# Bandpass.net
KiCad netlist of a schematic drawn in Altium Designer
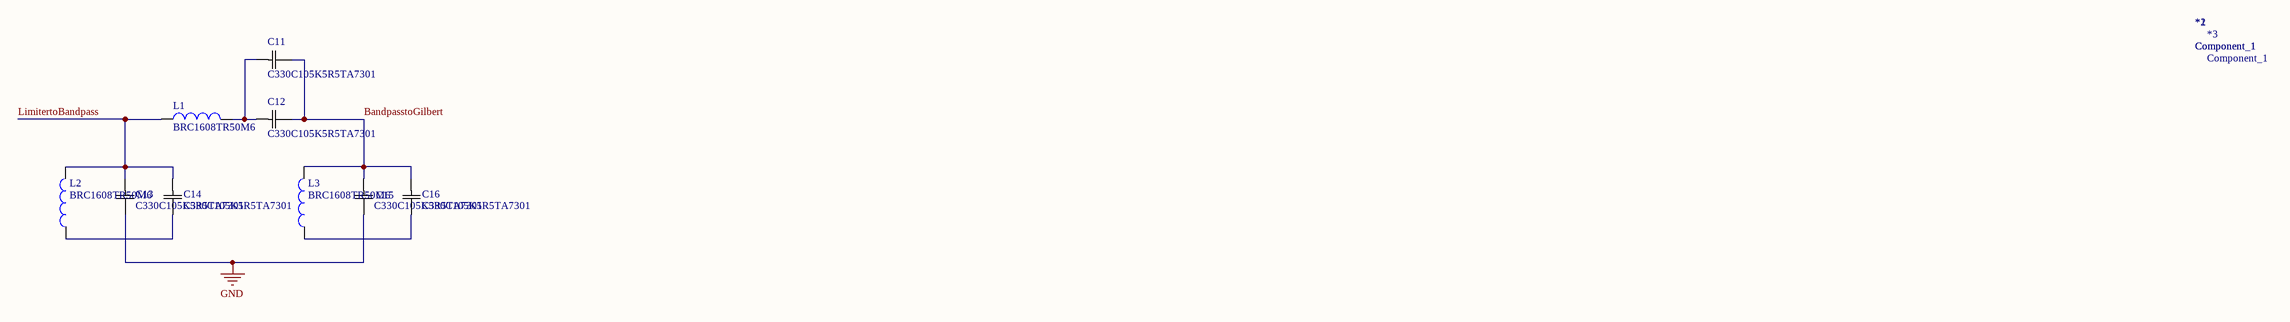
[diagram p0: Bandpass.SchDoc]

(export (version "E")
  (design (tool "Eeschema 10.0.6"))
  (components
    (comp (ref "*1") (value "Component_1") (libsource (lib "PRPC004SAAN-RC") (part "Component_1")))
    (comp (ref "*2") (value "Component_1") (libsource (lib "PRPC004SAAN-RC") (part "Component_1")))
    (comp (ref "*3") (value "Component_1") (libsource (lib "PRPC004SAAN-RC") (part "Component_1")))
    (comp (ref "C11")
      (value "C330C105K5R5TA7301")
      (footprint "CAP_C330C_MR_X7R_KEM")
      (description "No Description Available")
      (libsource (lib "C330C105K5R5TA7301") (part "C330C105K5R5TA7301"))
    )
    (comp (ref "C12")
      (value "C330C105K5R5TA7301")
      (footprint "CAP_C330C_MR_X7R_KEM")
      (description "No Description Available")
      (libsource (lib "C330C105K5R5TA7301") (part "C330C105K5R5TA7301"))
    )
    (comp (ref "C13")
      (value "C330C105K5R5TA7301")
      (footprint "CAP_C330C_MR_X7R_KEM")
      (description "No Description Available")
      (libsource (lib "C330C105K5R5TA7301") (part "C330C105K5R5TA7301"))
    )
    (comp (ref "C14")
      (value "C330C105K5R5TA7301")
      (footprint "CAP_C330C_MR_X7R_KEM")
      (description "No Description Available")
      (libsource (lib "C330C105K5R5TA7301") (part "C330C105K5R5TA7301"))
    )
    (comp (ref "C15")
      (value "C330C105K5R5TA7301")
      (footprint "CAP_C330C_MR_X7R_KEM")
      (description "No Description Available")
      (libsource (lib "C330C105K5R5TA7301") (part "C330C105K5R5TA7301"))
    )
    (comp (ref "C16")
      (value "C330C105K5R5TA7301")
      (footprint "CAP_C330C_MR_X7R_KEM")
      (description "No Description Available")
      (libsource (lib "C330C105K5R5TA7301") (part "C330C105K5R5TA7301"))
    )
    (comp (ref "L1")
      (value "BRC1608TR50M6")
      (footprint "INDC1608X100N")
      (description "Inductor Power Chip Wirewound 500nH 20% 6MHz Ferrite 1.05A 117mOhm DCR 0603 T/R")
      (libsource (lib "BRC1608TR50M6") (part "BRC1608TR50M6"))
    )
    (comp (ref "L2")
      (value "BRC1608TR50M6")
      (footprint "INDC1608X100N")
      (description "Inductor Power Chip Wirewound 500nH 20% 6MHz Ferrite 1.05A 117mOhm DCR 0603 T/R")
      (libsource (lib "BRC1608TR50M6") (part "BRC1608TR50M6"))
    )
    (comp (ref "L3")
      (value "BRC1608TR50M6")
      (footprint "INDC1608X100N")
      (description "Inductor Power Chip Wirewound 500nH 20% 6MHz Ferrite 1.05A 117mOhm DCR 0603 T/R")
      (libsource (lib "BRC1608TR50M6") (part "BRC1608TR50M6"))
    )
  )
  (nets
    (net (code "1") (name "/BandpasstoGilbert") (class "Default")
      (node (ref "C11") (pin "2") (pinfunction "2_2") (pintype "passive"))
      (node (ref "C12") (pin "2") (pinfunction "2_2") (pintype "passive"))
      (node (ref "C15") (pin "1") (pinfunction "1_1") (pintype "passive"))
      (node (ref "C16") (pin "1") (pinfunction "1_1") (pintype "passive"))
      (node (ref "L3") (pin "2") (pinfunction "2_2") (pintype "passive"))
    )
    (net (code "2") (name "/LimitertoBandpass") (class "Default")
      (node (ref "C13") (pin "1") (pinfunction "1_1") (pintype "passive"))
      (node (ref "C14") (pin "1") (pinfunction "1_1") (pintype "passive"))
      (node (ref "L1") (pin "1") (pinfunction "1_1") (pintype "passive"))
      (node (ref "L2") (pin "2") (pinfunction "2_2") (pintype "passive"))
    )
    (net (code "3") (name "GND") (class "Default")
      (node (ref "C13") (pin "2") (pinfunction "2_2") (pintype "passive"))
      (node (ref "C15") (pin "2") (pinfunction "2_2") (pintype "passive"))
    )
    (net (code "4") (name "Net-(C11-Pad1)") (class "Default")
      (node (ref "C11") (pin "1") (pinfunction "1_1") (pintype "passive"))
      (node (ref "C12") (pin "1") (pinfunction "1_1") (pintype "passive"))
      (node (ref "L1") (pin "2") (pinfunction "2_2") (pintype "passive"))
    )
    (net (code "5") (name "Net-(C14-Pad2)") (class "Default")
      (node (ref "C14") (pin "2") (pinfunction "2_2") (pintype "passive"))
      (node (ref "L2") (pin "1") (pinfunction "1_1") (pintype "passive"))
    )
    (net (code "6") (name "Net-(C16-Pad2)") (class "Default")
      (node (ref "C16") (pin "2") (pinfunction "2_2") (pintype "passive"))
      (node (ref "L3") (pin "1") (pinfunction "1_1") (pintype "passive"))
    )
  )
)
